# HallE.net
KiCad netlist of a schematic drawn in EAGLE
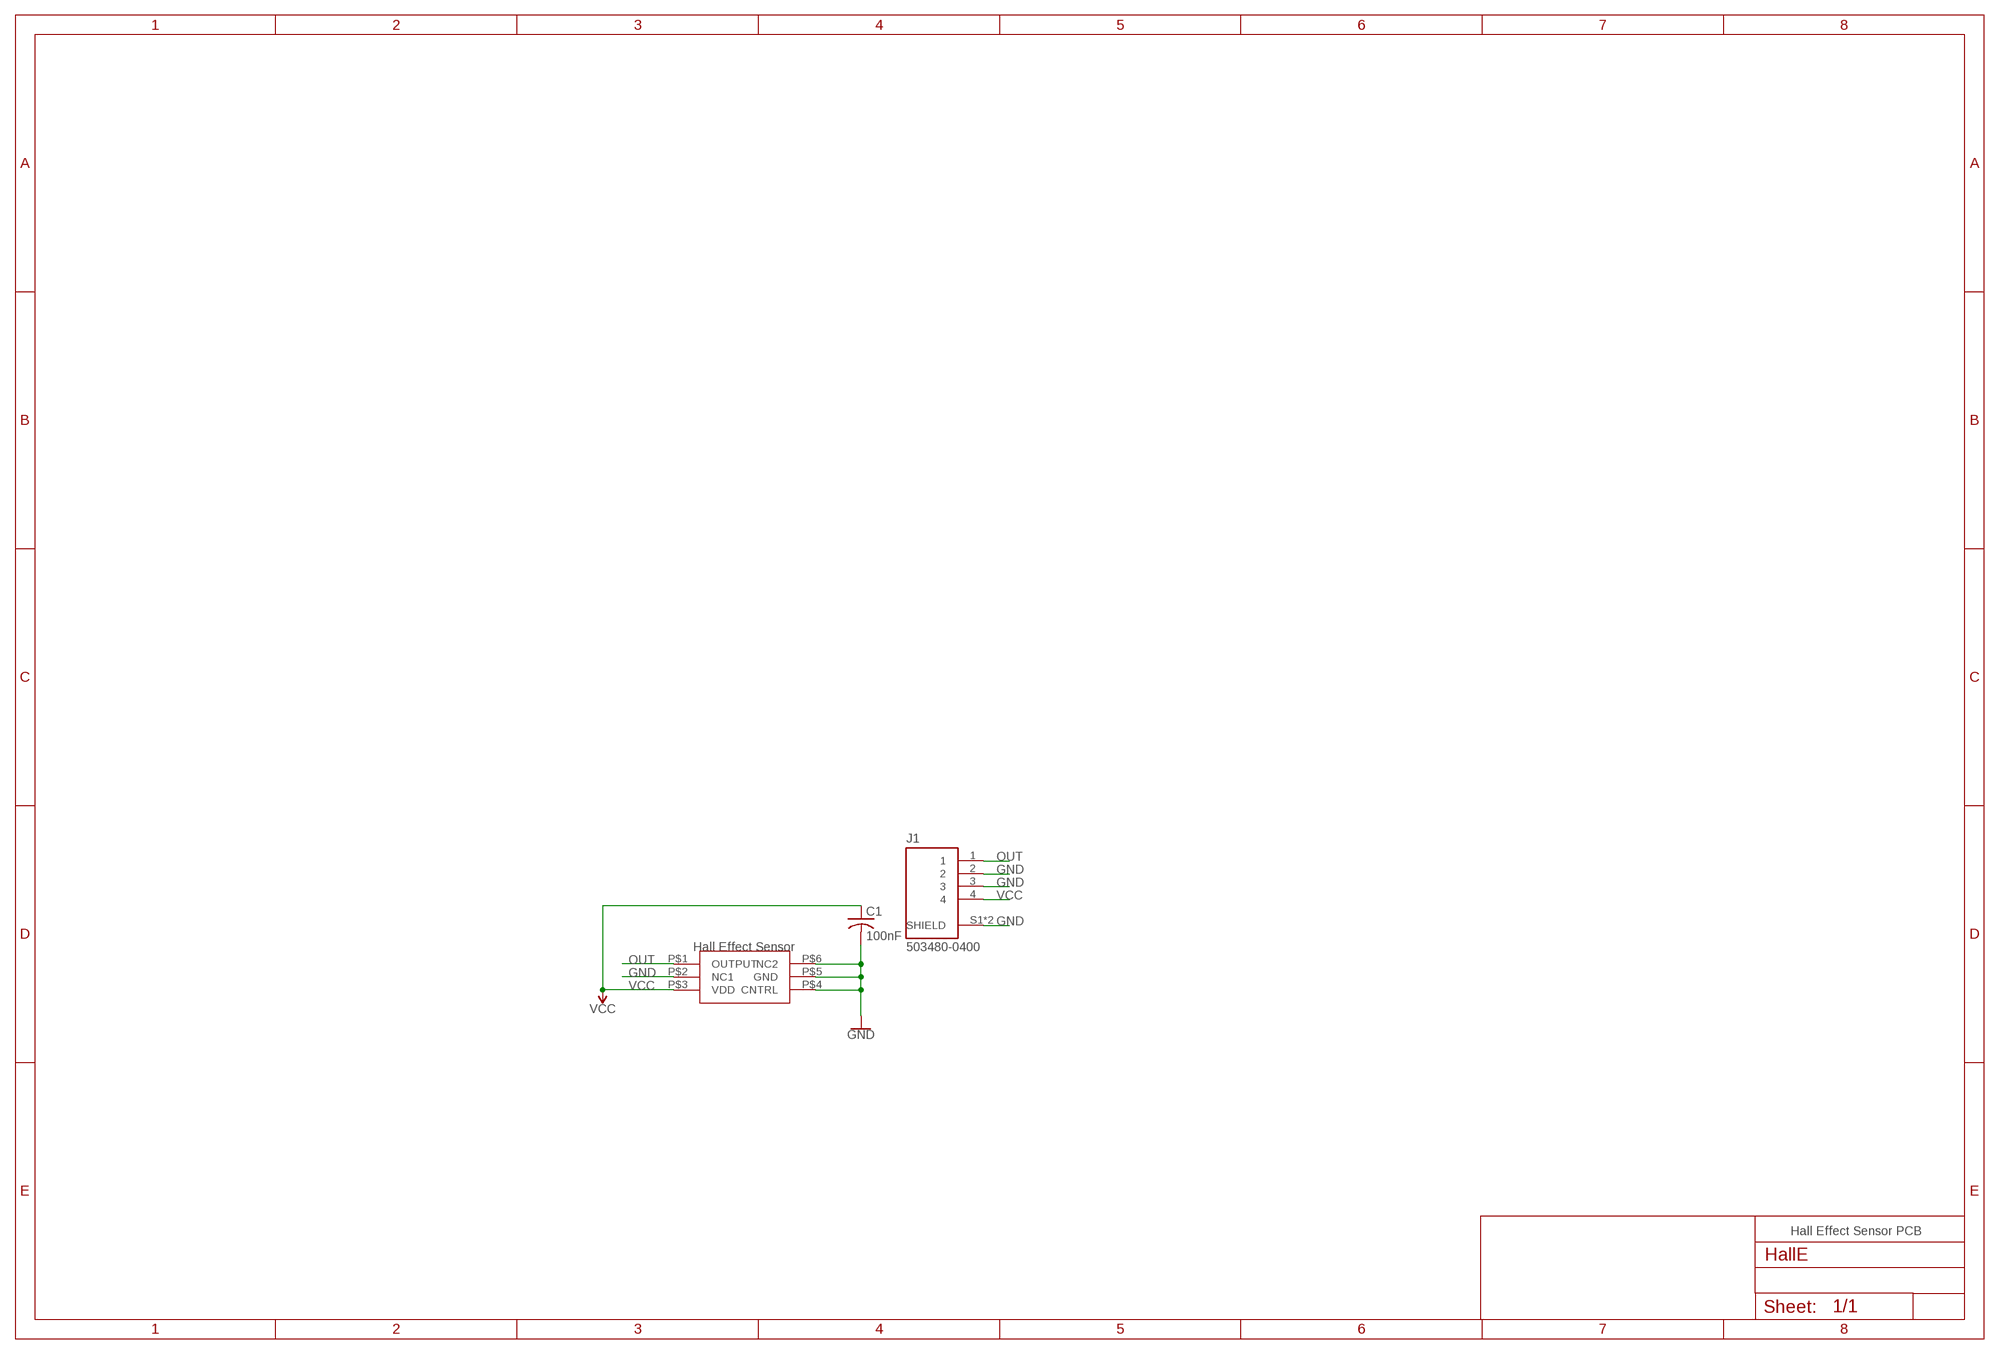
[diagram p0: schematic, sheet 1]

(export (version "E")
  (design (tool "Eeschema 10.0.6"))
  (components
    (comp (ref "C1")
      (value "100nF")
      (footprint "eagle-import:C0805")
      (libsource (lib "eagle-import") (part "C-USC0805"))
    )
    (comp (ref "J1")
      (value "503480-0400")
      (footprint "eagle-import:MOLEX_503480-0400")
      (fields
        (field (name "DIGI-KEY_PART_NUMBER") "WM1386CT-ND")
        (field (name "MF") "Molex")
        (field (name "MP") "5034800400")
      )
      (libsource (lib "eagle-import") (part "503480-0400"))
    )
    (comp (ref "U$1")
      (value "AH8503")
      (footprint "eagle-import:UDFN-6")
      (libsource (lib "eagle-import") (part "AH8503"))
    )
  )
  (nets
    (net (code "1") (name "/OUT") (class "Default")
      (node (ref "J1") (pin "1") (pinfunction "1_1") (pintype "passive"))
      (node (ref "U$1") (pin "P$1") (pinfunction "OUTPUT_P$1") (pintype "bidirectional"))
    )
    (net (code "2") (name "GND") (class "Default")
      (node (ref "C1") (pin "2") (pinfunction "2_2") (pintype "passive"))
      (node (ref "J1") (pin "2") (pinfunction "2_2") (pintype "passive"))
      (node (ref "J1") (pin "3") (pinfunction "3_3") (pintype "passive"))
      (node (ref "J1") (pin "S1") (pinfunction "SHIELD_S1") (pintype "passive"))
      (node (ref "J1") (pin "S2") (pinfunction "SHIELD_S2") (pintype "passive"))
      (node (ref "U$1") (pin "P$2") (pinfunction "NC1_P$2") (pintype "bidirectional"))
      (node (ref "U$1") (pin "P$4") (pinfunction "CNTRL_P$4") (pintype "bidirectional"))
      (node (ref "U$1") (pin "P$5") (pinfunction "GND_P$5") (pintype "bidirectional"))
      (node (ref "U$1") (pin "P$6") (pinfunction "NC2_P$6") (pintype "bidirectional"))
    )
    (net (code "3") (name "VCC") (class "Default")
      (node (ref "C1") (pin "1") (pinfunction "1_1") (pintype "passive"))
      (node (ref "J1") (pin "4") (pinfunction "4_4") (pintype "passive"))
      (node (ref "U$1") (pin "P$3") (pinfunction "VDD_P$3") (pintype "bidirectional"))
    )
  )
)
